# 09-PL_BANKS_34_35.net
KiCad netlist of a schematic drawn in Altium Designer
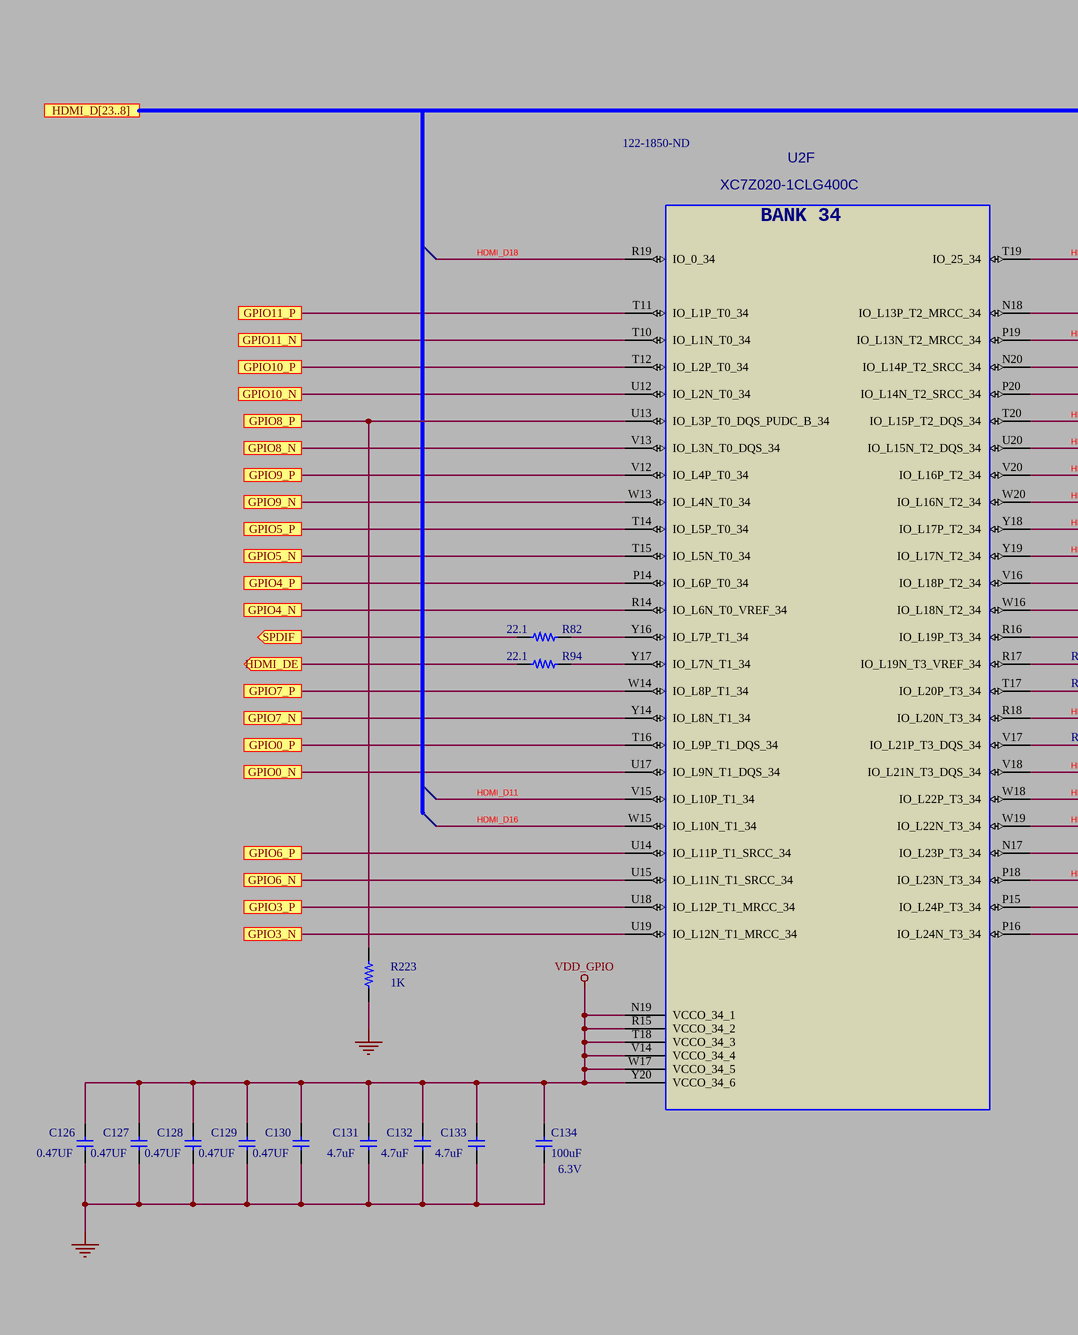
[diagram p0: 09-PL BANKS 34 & 35.SchDoc, left]
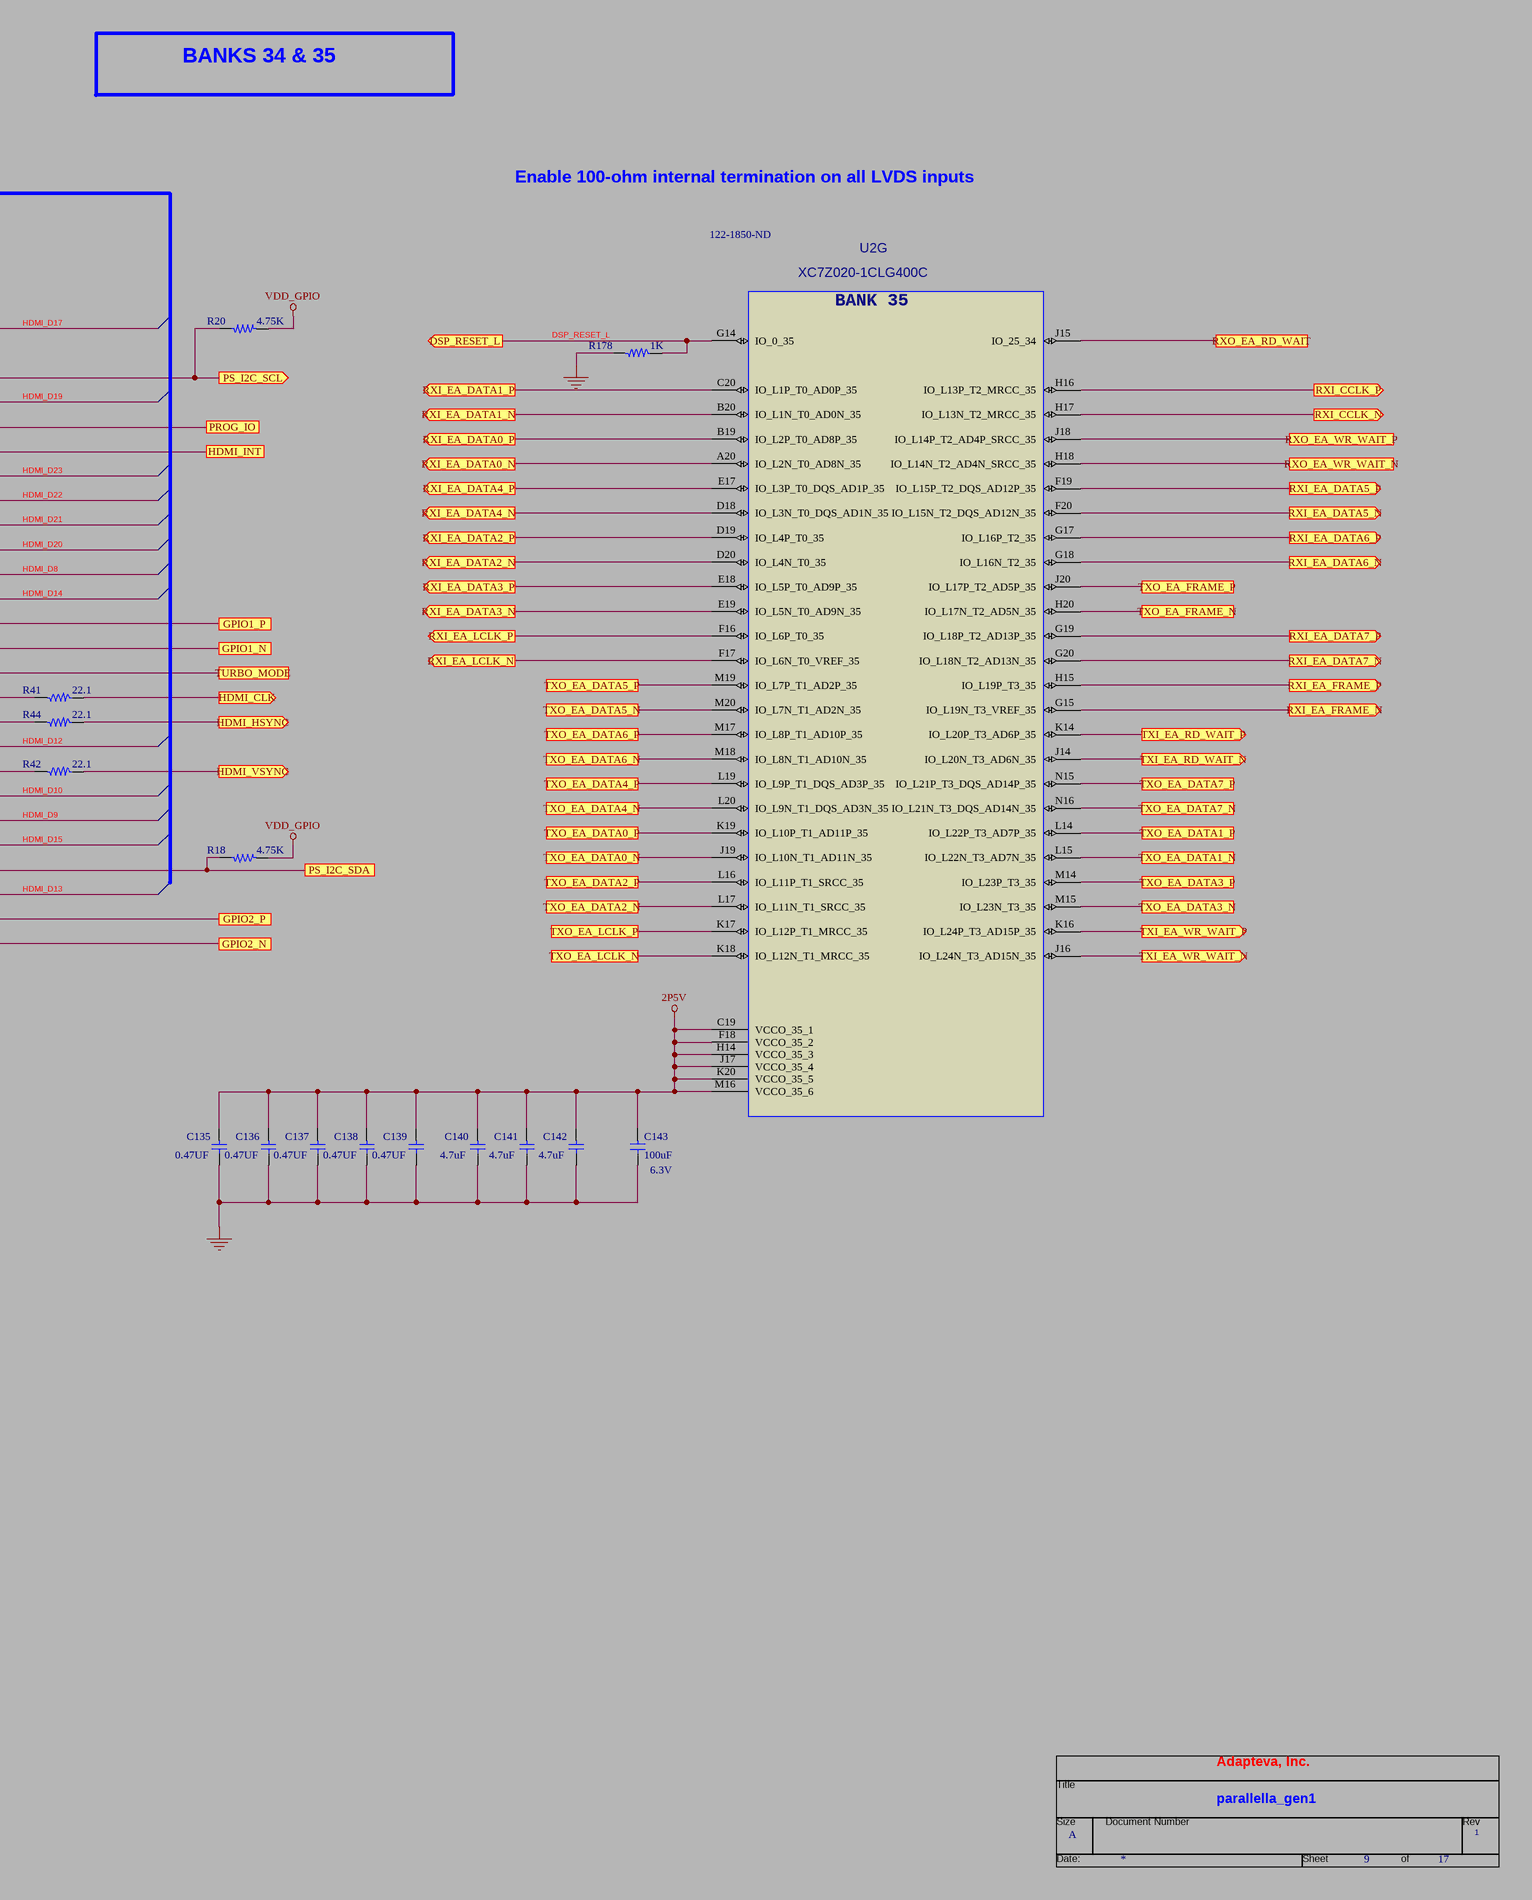
[diagram p1: 09-PL BANKS 34 & 35.SchDoc, right]

(export (version "E")
  (design (tool "Eeschema 10.0.6"))
  (components
    (comp (ref "C126")
      (value "0.47UF")
      (footprint "C0402")
      (description "CAP, 0402, 0.47UF, X5R, 16V")
      (fields (field (name "MFG") "TDK") (field (name "MFG PART NO") "C1005X5R1C474K"))
      (libsource (lib "*") (part "CAP0402_0P47UF_X5R"))
    )
    (comp (ref "C127")
      (value "0.47UF")
      (footprint "C0402")
      (description "CAP, 0402, 0.47UF, X5R, 16V")
      (fields (field (name "MFG") "TDK") (field (name "MFG PART NO") "C1005X5R1C474K"))
      (libsource (lib "*") (part "CAP0402_0P47UF_X5R"))
    )
    (comp (ref "C128")
      (value "0.47UF")
      (footprint "C0402")
      (description "CAP, 0402, 0.47UF, X5R, 16V")
      (fields (field (name "MFG") "TDK") (field (name "MFG PART NO") "C1005X5R1C474K"))
      (libsource (lib "*") (part "CAP0402_0P47UF_X5R"))
    )
    (comp (ref "C129")
      (value "0.47UF")
      (footprint "C0402")
      (description "CAP, 0402, 0.47UF, X5R, 16V")
      (fields (field (name "MFG") "TDK") (field (name "MFG PART NO") "C1005X5R1C474K"))
      (libsource (lib "*") (part "CAP0402_0P47UF_X5R"))
    )
    (comp (ref "C130")
      (value "0.47UF")
      (footprint "C0402")
      (description "CAP, 0402, 0.47UF, X5R, 16V")
      (fields (field (name "MFG") "TDK") (field (name "MFG PART NO") "C1005X5R1C474K"))
      (libsource (lib "*") (part "CAP0402_0P47UF_X5R"))
    )
    (comp (ref "C131")
      (value "4.7uF")
      (footprint "C0402")
      (description "CAP, 0402, 4.7UF, X5R, 6.3V")
      (fields (field (name "MFG PART NO") "C1005X5R0J475K") (field (name "MFG") "TDK"))
      (libsource (lib "*") (part "CAP0402_4P7UF_X5R"))
    )
    (comp (ref "C132")
      (value "4.7uF")
      (footprint "C0402")
      (description "CAP, 0402, 4.7UF, X5R, 6.3V")
      (fields (field (name "MFG PART NO") "C1005X5R0J475K") (field (name "MFG") "TDK"))
      (libsource (lib "*") (part "CAP0402_4P7UF_X5R"))
    )
    (comp (ref "C133")
      (value "4.7uF")
      (footprint "C0402")
      (description "CAP, 0402, 4.7UF, X5R, 6.3V")
      (fields (field (name "MFG PART NO") "C1005X5R0J475K") (field (name "MFG") "TDK"))
      (libsource (lib "*") (part "CAP0402_4P7UF_X5R"))
    )
    (comp (ref "C134")
      (value "100uF")
      (footprint "C1210")
      (description "CAP, 1210, 100UF, X5R, 6.3V, LOW ESR")
      (fields
        (field (name "VOLTAGE") "6.3V")
        (field (name "MFG PART NO") "GRM32ER60J107ME20L")
        (field (name "MFG") "MURATA")
      )
      (libsource (lib "*") (part "CAP1210_100UF_X5R_LOESR"))
    )
    (comp (ref "C135")
      (value "0.47UF")
      (footprint "C0402")
      (description "CAP, 0402, 0.47UF, X5R, 16V")
      (fields (field (name "MFG") "TDK") (field (name "MFG PART NO") "C1005X5R1C474K"))
      (libsource (lib "*") (part "CAP0402_0P47UF_X5R"))
    )
    (comp (ref "C136")
      (value "0.47UF")
      (footprint "C0402")
      (description "CAP, 0402, 0.47UF, X5R, 16V")
      (fields (field (name "MFG") "TDK") (field (name "MFG PART NO") "C1005X5R1C474K"))
      (libsource (lib "*") (part "CAP0402_0P47UF_X5R"))
    )
    (comp (ref "C137")
      (value "0.47UF")
      (footprint "C0402")
      (description "CAP, 0402, 0.47UF, X5R, 16V")
      (fields (field (name "MFG") "TDK") (field (name "MFG PART NO") "C1005X5R1C474K"))
      (libsource (lib "*") (part "CAP0402_0P47UF_X5R"))
    )
    (comp (ref "C138")
      (value "0.47UF")
      (footprint "C0402")
      (description "CAP, 0402, 0.47UF, X5R, 16V")
      (fields (field (name "MFG") "TDK") (field (name "MFG PART NO") "C1005X5R1C474K"))
      (libsource (lib "*") (part "CAP0402_0P47UF_X5R"))
    )
    (comp (ref "C139")
      (value "0.47UF")
      (footprint "C0402")
      (description "CAP, 0402, 0.47UF, X5R, 16V")
      (fields (field (name "MFG") "TDK") (field (name "MFG PART NO") "C1005X5R1C474K"))
      (libsource (lib "*") (part "CAP0402_0P47UF_X5R"))
    )
    (comp (ref "C140")
      (value "4.7uF")
      (footprint "C0402")
      (description "CAP, 0402, 4.7UF, X5R, 6.3V")
      (fields (field (name "MFG PART NO") "C1005X5R0J475K") (field (name "MFG") "TDK"))
      (libsource (lib "*") (part "CAP0402_4P7UF_X5R"))
    )
    (comp (ref "C141")
      (value "4.7uF")
      (footprint "C0402")
      (description "CAP, 0402, 4.7UF, X5R, 6.3V")
      (fields (field (name "MFG PART NO") "C1005X5R0J475K") (field (name "MFG") "TDK"))
      (libsource (lib "*") (part "CAP0402_4P7UF_X5R"))
    )
    (comp (ref "C142")
      (value "4.7uF")
      (footprint "C0402")
      (description "CAP, 0402, 4.7UF, X5R, 6.3V")
      (fields (field (name "MFG PART NO") "C1005X5R0J475K") (field (name "MFG") "TDK"))
      (libsource (lib "*") (part "CAP0402_4P7UF_X5R"))
    )
    (comp (ref "C143")
      (value "100uF")
      (footprint "C1210")
      (description "CAP, 1210, 100UF, X5R, 6.3V, LOW ESR")
      (fields
        (field (name "VOLTAGE") "6.3V")
        (field (name "MFG PART NO") "GRM32ER60J107ME20L")
        (field (name "MFG") "MURATA")
      )
      (libsource (lib "*") (part "CAP1210_100UF_X5R_LOESR"))
    )
    (comp (ref "R18")
      (value "4.75K")
      (footprint "R0402")
      (description "RES, 0402, 4.75K, 1%")
      (fields (field (name "MFG") "VISHAY") (field (name "MFG PART NO") "CRCW04024K75FKED"))
      (libsource (lib "*") (part "RES0402_4K75"))
    )
    (comp (ref "R20")
      (value "4.75K")
      (footprint "R0402")
      (description "RES, 0402, 4.75K, 1%")
      (fields (field (name "MFG") "VISHAY") (field (name "MFG PART NO") "CRCW04024K75FKED"))
      (libsource (lib "*") (part "RES0402_4K75"))
    )
    (comp (ref "R41")
      (value "22.1")
      (footprint "R0402")
      (description "RES, 0402, 22.1, 1%")
      (fields (field (name "MFG") "VISHAY") (field (name "MFG PART NO") "CRCW040222R1FKED"))
      (libsource (lib "*") (part "RES0402_22R1"))
    )
    (comp (ref "R42")
      (value "22.1")
      (footprint "R0402")
      (description "RES, 0402, 22.1, 1%")
      (fields (field (name "MFG") "VISHAY") (field (name "MFG PART NO") "CRCW040222R1FKED"))
      (libsource (lib "*") (part "RES0402_22R1"))
    )
    (comp (ref "R44")
      (value "22.1")
      (footprint "R0402")
      (description "RES, 0402, 22.1, 1%")
      (fields (field (name "MFG") "VISHAY") (field (name "MFG PART NO") "CRCW040222R1FKED"))
      (libsource (lib "*") (part "RES0402_22R1"))
    )
    (comp (ref "R82")
      (value "22.1")
      (footprint "R0402")
      (description "RES, 0402, 22.1, 1%")
      (fields (field (name "MFG") "VISHAY") (field (name "MFG PART NO") "CRCW040222R1FKED"))
      (libsource (lib "*") (part "RES0402_22R1"))
    )
    (comp (ref "R94")
      (value "22.1")
      (footprint "R0402")
      (description "RES, 0402, 22.1, 1%")
      (fields (field (name "MFG") "VISHAY") (field (name "MFG PART NO") "CRCW040222R1FKED"))
      (libsource (lib "*") (part "RES0402_22R1"))
    )
    (comp (ref "R178")
      (value "1K")
      (footprint "R0402")
      (description "RES, 0402, 1K")
      (fields (field (name "MFG") "VISHAY") (field (name "MFG PART NO") "CRCW04021K00FKED"))
      (libsource (lib "*") (part "RES0402_1K"))
    )
    (comp (ref "R223")
      (value "1K")
      (footprint "R0402")
      (description "RES, 0402, 1K")
      (fields (field (name "MFG") "VISHAY") (field (name "MFG PART NO") "CRCW04021K00FKED"))
      (libsource (lib "*") (part "RES0402_1K"))
    )
    (comp (ref "U2")
      (value "7Z020-CLG400")
      (footprint "CBGA400_17SQ_1P6H_P8MMP")
      (description "IC, EPP, XILINX, ZYNQ, 7Z020, CLG400")
      (fields
        (field (name "VENDOR PN") "XC7Z020-1CLG400C")
        (field (name "SUPPLIER PART NUMBER 1") "122-1850-ND")
      )
      (libsource (lib "*") (part "ZYNQ_7Z020_CLG400"))
    )
  )
  (nets
    (net (code "1") (name "/DSP_RESET_L") (class "Default")
      (node (ref "R178") (pin "2") (pinfunction "2_2") (pintype "passive"))
      (node (ref "U2") (pin "G14") (pinfunction "IO_0_35_G14") (pintype "bidirectional"))
    )
    (net (code "2") (name "/GPIO0_N") (class "Default")
      (node (ref "U2") (pin "U17") (pinfunction "IO_L9N_T1_DQS_34_U17") (pintype "bidirectional"))
    )
    (net (code "3") (name "/GPIO0_P") (class "Default")
      (node (ref "U2") (pin "T16") (pinfunction "IO_L9P_T1_DQS_34_T16") (pintype "bidirectional"))
    )
    (net (code "4") (name "/GPIO1_N") (class "Default")
      (node (ref "U2") (pin "W16") (pinfunction "IO_L18N_T2_34_W16") (pintype "bidirectional"))
    )
    (net (code "5") (name "/GPIO1_P") (class "Default")
      (node (ref "U2") (pin "V16") (pinfunction "IO_L18P_T2_34_V16") (pintype "bidirectional"))
    )
    (net (code "6") (name "/GPIO2_N") (class "Default")
      (node (ref "U2") (pin "P16") (pinfunction "IO_L24N_T3_34_P16") (pintype "bidirectional"))
    )
    (net (code "7") (name "/GPIO2_P") (class "Default")
      (node (ref "U2") (pin "P15") (pinfunction "IO_L24P_T3_34_P15") (pintype "bidirectional"))
    )
    (net (code "8") (name "/GPIO3_N") (class "Default")
      (node (ref "U2") (pin "U19") (pinfunction "IO_L12N_T1_MRCC_34_U19") (pintype "bidirectional"))
    )
    (net (code "9") (name "/GPIO3_P") (class "Default")
      (node (ref "U2") (pin "U18") (pinfunction "IO_L12P_T1_MRCC_34_U18") (pintype "bidirectional"))
    )
    (net (code "10") (name "/GPIO4_N") (class "Default")
      (node (ref "U2") (pin "R14") (pinfunction "IO_L6N_T0_VREF_34_R14") (pintype "bidirectional"))
    )
    (net (code "11") (name "/GPIO4_P") (class "Default")
      (node (ref "U2") (pin "P14") (pinfunction "IO_L6P_T0_34_P14") (pintype "bidirectional"))
    )
    (net (code "12") (name "/GPIO5_N") (class "Default")
      (node (ref "U2") (pin "T15") (pinfunction "IO_L5N_T0_34_T15") (pintype "bidirectional"))
    )
    (net (code "13") (name "/GPIO5_P") (class "Default")
      (node (ref "U2") (pin "T14") (pinfunction "IO_L5P_T0_34_T14") (pintype "bidirectional"))
    )
    (net (code "14") (name "/GPIO6_N") (class "Default")
      (node (ref "U2") (pin "U15") (pinfunction "IO_L11N_T1_SRCC_34_U15") (pintype "bidirectional"))
    )
    (net (code "15") (name "/GPIO6_P") (class "Default")
      (node (ref "U2") (pin "U14") (pinfunction "IO_L11P_T1_SRCC_34_U14") (pintype "bidirectional"))
    )
    (net (code "16") (name "/GPIO7_N") (class "Default")
      (node (ref "U2") (pin "Y14") (pinfunction "IO_L8N_T1_34_Y14") (pintype "bidirectional"))
    )
    (net (code "17") (name "/GPIO7_P") (class "Default")
      (node (ref "U2") (pin "W14") (pinfunction "IO_L8P_T1_34_W14") (pintype "bidirectional"))
    )
    (net (code "18") (name "/GPIO8_N") (class "Default")
      (node (ref "U2") (pin "V13") (pinfunction "IO_L3N_T0_DQS_34_V13") (pintype "bidirectional"))
    )
    (net (code "19") (name "/GPIO8_P") (class "Default")
      (node (ref "R223") (pin "2") (pinfunction "2_2") (pintype "passive"))
      (node (ref "U2") (pin "U13") (pinfunction "IO_L3P_T0_DQS_PUDC_B_34_U13") (pintype "bidirectional"))
    )
    (net (code "20") (name "/GPIO9_N") (class "Default")
      (node (ref "U2") (pin "W13") (pinfunction "IO_L4N_T0_34_W13") (pintype "bidirectional"))
    )
    (net (code "21") (name "/GPIO9_P") (class "Default")
      (node (ref "U2") (pin "V12") (pinfunction "IO_L4P_T0_34_V12") (pintype "bidirectional"))
    )
    (net (code "22") (name "/GPIO10_N") (class "Default")
      (node (ref "U2") (pin "U12") (pinfunction "IO_L2N_T0_34_U12") (pintype "bidirectional"))
    )
    (net (code "23") (name "/GPIO10_P") (class "Default")
      (node (ref "U2") (pin "T12") (pinfunction "IO_L2P_T0_34_T12") (pintype "bidirectional"))
    )
    (net (code "24") (name "/GPIO11_N") (class "Default")
      (node (ref "U2") (pin "T10") (pinfunction "IO_L1N_T0_34_T10") (pintype "bidirectional"))
    )
    (net (code "25") (name "/GPIO11_P") (class "Default")
      (node (ref "U2") (pin "T11") (pinfunction "IO_L1P_T0_34_T11") (pintype "bidirectional"))
    )
    (net (code "26") (name "/HDMI_CLK") (class "Default")
      (node (ref "R41") (pin "2") (pinfunction "2_2") (pintype "passive"))
    )
    (net (code "27") (name "/HDMI_D8") (class "Default")
      (node (ref "U2") (pin "Y18") (pinfunction "IO_L17P_T2_34_Y18") (pintype "bidirectional"))
    )
    (net (code "28") (name "/HDMI_D9") (class "Default")
      (node (ref "U2") (pin "W18") (pinfunction "IO_L22P_T3_34_W18") (pintype "bidirectional"))
    )
    (net (code "29") (name "/HDMI_D10") (class "Default")
      (node (ref "U2") (pin "V18") (pinfunction "IO_L21N_T3_DQS_34_V18") (pintype "bidirectional"))
    )
    (net (code "30") (name "/HDMI_D11") (class "Default")
      (node (ref "U2") (pin "V15") (pinfunction "IO_L10P_T1_34_V15") (pintype "bidirectional"))
    )
    (net (code "31") (name "/HDMI_D12") (class "Default")
      (node (ref "U2") (pin "R18") (pinfunction "IO_L20N_T3_34_R18") (pintype "bidirectional"))
    )
    (net (code "32") (name "/HDMI_D13") (class "Default")
      (node (ref "U2") (pin "P18") (pinfunction "IO_L23N_T3_34_P18") (pintype "bidirectional"))
    )
    (net (code "33") (name "/HDMI_D14") (class "Default")
      (node (ref "U2") (pin "Y19") (pinfunction "IO_L17N_T2_34_Y19") (pintype "bidirectional"))
    )
    (net (code "34") (name "/HDMI_D15") (class "Default")
      (node (ref "U2") (pin "W19") (pinfunction "IO_L22N_T3_34_W19") (pintype "bidirectional"))
    )
    (net (code "35") (name "/HDMI_D16") (class "Default")
      (node (ref "U2") (pin "W15") (pinfunction "IO_L10N_T1_34_W15") (pintype "bidirectional"))
    )
    (net (code "36") (name "/HDMI_D17") (class "Default")
      (node (ref "U2") (pin "T19") (pinfunction "IO_25_34_T19") (pintype "bidirectional"))
    )
    (net (code "37") (name "/HDMI_D18") (class "Default")
      (node (ref "U2") (pin "R19") (pinfunction "IO_0_34_R19") (pintype "bidirectional"))
    )
    (net (code "38") (name "/HDMI_D19") (class "Default")
      (node (ref "U2") (pin "P19") (pinfunction "IO_L13N_T2_MRCC_34_P19") (pintype "bidirectional"))
    )
    (net (code "39") (name "/HDMI_D20") (class "Default")
      (node (ref "U2") (pin "W20") (pinfunction "IO_L16N_T2_34_W20") (pintype "bidirectional"))
    )
    (net (code "40") (name "/HDMI_D21") (class "Default")
      (node (ref "U2") (pin "V20") (pinfunction "IO_L16P_T2_34_V20") (pintype "bidirectional"))
    )
    (net (code "41") (name "/HDMI_D22") (class "Default")
      (node (ref "U2") (pin "U20") (pinfunction "IO_L15N_T2_DQS_34_U20") (pintype "bidirectional"))
    )
    (net (code "42") (name "/HDMI_D23") (class "Default")
      (node (ref "U2") (pin "T20") (pinfunction "IO_L15P_T2_DQS_34_T20") (pintype "bidirectional"))
    )
    (net (code "43") (name "/HDMI_DE") (class "Default")
      (node (ref "R94") (pin "2") (pinfunction "2_2") (pintype "passive"))
    )
    (net (code "45") (name "/HDMI_HSYNC") (class "Default")
      (node (ref "R44") (pin "2") (pinfunction "2_2") (pintype "passive"))
    )
    (net (code "46") (name "/HDMI_INT") (class "Default")
      (node (ref "U2") (pin "P20") (pinfunction "IO_L14N_T2_SRCC_34_P20") (pintype "bidirectional"))
    )
    (net (code "47") (name "/HDMI_VSYNC") (class "Default")
      (node (ref "R42") (pin "2") (pinfunction "2_2") (pintype "passive"))
    )
    (net (code "48") (name "/PROG_IO") (class "Default")
      (node (ref "U2") (pin "N20") (pinfunction "IO_L14P_T2_SRCC_34_N20") (pintype "bidirectional"))
    )
    (net (code "49") (name "/PS_I2C_SCL") (class "Default")
      (node (ref "R20") (pin "2") (pinfunction "2_2") (pintype "passive"))
      (node (ref "U2") (pin "N18") (pinfunction "IO_L13P_T2_MRCC_34_N18") (pintype "bidirectional"))
    )
    (net (code "50") (name "/PS_I2C_SDA") (class "Default")
      (node (ref "R18") (pin "2") (pinfunction "2_2") (pintype "passive"))
      (node (ref "U2") (pin "N17") (pinfunction "IO_L23P_T3_34_N17") (pintype "bidirectional"))
    )
    (net (code "51") (name "/RXI_CCLK_N") (class "Default")
      (node (ref "U2") (pin "H17") (pinfunction "IO_L13N_T2_MRCC_35_H17") (pintype "bidirectional"))
    )
    (net (code "52") (name "/RXI_CCLK_P") (class "Default")
      (node (ref "U2") (pin "H16") (pinfunction "IO_L13P_T2_MRCC_35_H16") (pintype "bidirectional"))
    )
    (net (code "53") (name "/RXI_EA_DATA0_N") (class "Default")
      (node (ref "U2") (pin "A20") (pinfunction "IO_L2N_T0_AD8N_35_A20") (pintype "bidirectional"))
    )
    (net (code "54") (name "/RXI_EA_DATA0_P") (class "Default")
      (node (ref "U2") (pin "B19") (pinfunction "IO_L2P_T0_AD8P_35_B19") (pintype "bidirectional"))
    )
    (net (code "55") (name "/RXI_EA_DATA1_N") (class "Default")
      (node (ref "U2") (pin "B20") (pinfunction "IO_L1N_T0_AD0N_35_B20") (pintype "bidirectional"))
    )
    (net (code "56") (name "/RXI_EA_DATA1_P") (class "Default")
      (node (ref "U2") (pin "C20") (pinfunction "IO_L1P_T0_AD0P_35_C20") (pintype "bidirectional"))
    )
    (net (code "57") (name "/RXI_EA_DATA2_N") (class "Default")
      (node (ref "U2") (pin "D20") (pinfunction "IO_L4N_T0_35_D20") (pintype "bidirectional"))
    )
    (net (code "58") (name "/RXI_EA_DATA2_P") (class "Default")
      (node (ref "U2") (pin "D19") (pinfunction "IO_L4P_T0_35_D19") (pintype "bidirectional"))
    )
    (net (code "59") (name "/RXI_EA_DATA3_N") (class "Default")
      (node (ref "U2") (pin "E19") (pinfunction "IO_L5N_T0_AD9N_35_E19") (pintype "bidirectional"))
    )
    (net (code "60") (name "/RXI_EA_DATA3_P") (class "Default")
      (node (ref "U2") (pin "E18") (pinfunction "IO_L5P_T0_AD9P_35_E18") (pintype "bidirectional"))
    )
    (net (code "61") (name "/RXI_EA_DATA4_N") (class "Default")
      (node (ref "U2") (pin "D18") (pinfunction "IO_L3N_T0_DQS_AD1N_35_D18") (pintype "bidirectional"))
    )
    (net (code "62") (name "/RXI_EA_DATA4_P") (class "Default")
      (node (ref "U2") (pin "E17") (pinfunction "IO_L3P_T0_DQS_AD1P_35_E17") (pintype "bidirectional"))
    )
    (net (code "63") (name "/RXI_EA_DATA5_N") (class "Default")
      (node (ref "U2") (pin "F20") (pinfunction "IO_L15N_T2_DQS_AD12N_35_F20") (pintype "bidirectional"))
    )
    (net (code "64") (name "/RXI_EA_DATA5_P") (class "Default")
      (node (ref "U2") (pin "F19") (pinfunction "IO_L15P_T2_DQS_AD12P_35_F19") (pintype "bidirectional"))
    )
    (net (code "65") (name "/RXI_EA_DATA6_N") (class "Default")
      (node (ref "U2") (pin "G18") (pinfunction "IO_L16N_T2_35_G18") (pintype "bidirectional"))
    )
    (net (code "66") (name "/RXI_EA_DATA6_P") (class "Default")
      (node (ref "U2") (pin "G17") (pinfunction "IO_L16P_T2_35_G17") (pintype "bidirectional"))
    )
    (net (code "67") (name "/RXI_EA_DATA7_N") (class "Default")
      (node (ref "U2") (pin "G20") (pinfunction "IO_L18N_T2_AD13N_35_G20") (pintype "bidirectional"))
    )
    (net (code "68") (name "/RXI_EA_DATA7_P") (class "Default")
      (node (ref "U2") (pin "G19") (pinfunction "IO_L18P_T2_AD13P_35_G19") (pintype "bidirectional"))
    )
    (net (code "69") (name "/RXI_EA_FRAME_N") (class "Default")
      (node (ref "U2") (pin "G15") (pinfunction "IO_L19N_T3_VREF_35_G15") (pintype "bidirectional"))
    )
    (net (code "70") (name "/RXI_EA_FRAME_P") (class "Default")
      (node (ref "U2") (pin "H15") (pinfunction "IO_L19P_T3_35_H15") (pintype "bidirectional"))
    )
    (net (code "71") (name "/RXI_EA_LCLK_N") (class "Default")
      (node (ref "U2") (pin "F17") (pinfunction "IO_L6N_T0_VREF_35_F17") (pintype "bidirectional"))
    )
    (net (code "72") (name "/RXI_EA_LCLK_P") (class "Default")
      (node (ref "U2") (pin "F16") (pinfunction "IO_L6P_T0_35_F16") (pintype "bidirectional"))
    )
    (net (code "73") (name "/RXO_EA_RD_WAIT") (class "Default")
      (node (ref "U2") (pin "J15") (pinfunction "IO_25_34_J15") (pintype "bidirectional"))
    )
    (net (code "74") (name "/RXO_EA_WR_WAIT_N") (class "Default")
      (node (ref "U2") (pin "H18") (pinfunction "IO_L14N_T2_AD4N_SRCC_35_H18") (pintype "bidirectional"))
    )
    (net (code "75") (name "/RXO_EA_WR_WAIT_P") (class "Default")
      (node (ref "U2") (pin "J18") (pinfunction "IO_L14P_T2_AD4P_SRCC_35_J18") (pintype "bidirectional"))
    )
    (net (code "76") (name "/SPDIF") (class "Default")
      (node (ref "R82") (pin "2") (pinfunction "2_2") (pintype "passive"))
    )
    (net (code "77") (name "/TURBO_MODE") (class "Default")
      (node (ref "U2") (pin "R16") (pinfunction "IO_L19P_T3_34_R16") (pintype "bidirectional"))
    )
    (net (code "78") (name "/TXI_EA_RD_WAIT_N") (class "Default")
      (node (ref "U2") (pin "J14") (pinfunction "IO_L20N_T3_AD6N_35_J14") (pintype "bidirectional"))
    )
    (net (code "79") (name "/TXI_EA_RD_WAIT_P") (class "Default")
      (node (ref "U2") (pin "K14") (pinfunction "IO_L20P_T3_AD6P_35_K14") (pintype "bidirectional"))
    )
    (net (code "80") (name "/TXI_EA_WR_WAIT_N") (class "Default")
      (node (ref "U2") (pin "J16") (pinfunction "IO_L24N_T3_AD15N_35_J16") (pintype "bidirectional"))
    )
    (net (code "81") (name "/TXI_EA_WR_WAIT_P") (class "Default")
      (node (ref "U2") (pin "K16") (pinfunction "IO_L24P_T3_AD15P_35_K16") (pintype "bidirectional"))
    )
    (net (code "82") (name "/TXO_EA_DATA0_N") (class "Default")
      (node (ref "U2") (pin "J19") (pinfunction "IO_L10N_T1_AD11N_35_J19") (pintype "bidirectional"))
    )
    (net (code "83") (name "/TXO_EA_DATA0_P") (class "Default")
      (node (ref "U2") (pin "K19") (pinfunction "IO_L10P_T1_AD11P_35_K19") (pintype "bidirectional"))
    )
    (net (code "84") (name "/TXO_EA_DATA1_N") (class "Default")
      (node (ref "U2") (pin "L15") (pinfunction "IO_L22N_T3_AD7N_35_L15") (pintype "bidirectional"))
    )
    (net (code "85") (name "/TXO_EA_DATA1_P") (class "Default")
      (node (ref "U2") (pin "L14") (pinfunction "IO_L22P_T3_AD7P_35_L14") (pintype "bidirectional"))
    )
    (net (code "86") (name "/TXO_EA_DATA2_N") (class "Default")
      (node (ref "U2") (pin "L17") (pinfunction "IO_L11N_T1_SRCC_35_L17") (pintype "bidirectional"))
    )
    (net (code "87") (name "/TXO_EA_DATA2_P") (class "Default")
      (node (ref "U2") (pin "L16") (pinfunction "IO_L11P_T1_SRCC_35_L16") (pintype "bidirectional"))
    )
    (net (code "88") (name "/TXO_EA_DATA3_N") (class "Default")
      (node (ref "U2") (pin "M15") (pinfunction "IO_L23N_T3_35_M15") (pintype "bidirectional"))
    )
    (net (code "89") (name "/TXO_EA_DATA3_P") (class "Default")
      (node (ref "U2") (pin "M14") (pinfunction "IO_L23P_T3_35_M14") (pintype "bidirectional"))
    )
    (net (code "90") (name "/TXO_EA_DATA4_N") (class "Default")
      (node (ref "U2") (pin "L20") (pinfunction "IO_L9N_T1_DQS_AD3N_35_L20") (pintype "bidirectional"))
    )
    (net (code "91") (name "/TXO_EA_DATA4_P") (class "Default")
      (node (ref "U2") (pin "L19") (pinfunction "IO_L9P_T1_DQS_AD3P_35_L19") (pintype "bidirectional"))
    )
    (net (code "92") (name "/TXO_EA_DATA5_N") (class "Default")
      (node (ref "U2") (pin "M20") (pinfunction "IO_L7N_T1_AD2N_35_M20") (pintype "bidirectional"))
    )
    (net (code "93") (name "/TXO_EA_DATA5_P") (class "Default")
      (node (ref "U2") (pin "M19") (pinfunction "IO_L7P_T1_AD2P_35_M19") (pintype "bidirectional"))
    )
    (net (code "94") (name "/TXO_EA_DATA6_N") (class "Default")
      (node (ref "U2") (pin "M18") (pinfunction "IO_L8N_T1_AD10N_35_M18") (pintype "bidirectional"))
    )
    (net (code "95") (name "/TXO_EA_DATA6_P") (class "Default")
      (node (ref "U2") (pin "M17") (pinfunction "IO_L8P_T1_AD10P_35_M17") (pintype "bidirectional"))
    )
    (net (code "96") (name "/TXO_EA_DATA7_N") (class "Default")
      (node (ref "U2") (pin "N16") (pinfunction "IO_L21N_T3_DQS_AD14N_35_N16") (pintype "bidirectional"))
    )
    (net (code "97") (name "/TXO_EA_DATA7_P") (class "Default")
      (node (ref "U2") (pin "N15") (pinfunction "IO_L21P_T3_DQS_AD14P_35_N15") (pintype "bidirectional"))
    )
    (net (code "98") (name "/TXO_EA_FRAME_N") (class "Default")
      (node (ref "U2") (pin "H20") (pinfunction "IO_L17N_T2_AD5N_35_H20") (pintype "bidirectional"))
    )
    (net (code "99") (name "/TXO_EA_FRAME_P") (class "Default")
      (node (ref "U2") (pin "J20") (pinfunction "IO_L17P_T2_AD5P_35_J20") (pintype "bidirectional"))
    )
    (net (code "100") (name "/TXO_EA_LCLK_N") (class "Default")
      (node (ref "U2") (pin "K18") (pinfunction "IO_L12N_T1_MRCC_35_K18") (pintype "bidirectional"))
    )
    (net (code "101") (name "/TXO_EA_LCLK_P") (class "Default")
      (node (ref "U2") (pin "K17") (pinfunction "IO_L12P_T1_MRCC_35_K17") (pintype "bidirectional"))
    )
    (net (code "102") (name "2P5V") (class "Default")
      (node (ref "C135") (pin "1") (pinfunction "1_1") (pintype "passive"))
      (node (ref "C136") (pin "1") (pinfunction "1_1") (pintype "passive"))
      (node (ref "C137") (pin "1") (pinfunction "1_1") (pintype "passive"))
      (node (ref "C138") (pin "1") (pinfunction "1_1") (pintype "passive"))
      (node (ref "C139") (pin "1") (pinfunction "1_1") (pintype "passive"))
      (node (ref "C140") (pin "1") (pinfunction "1_1") (pintype "passive"))
      (node (ref "C141") (pin "1") (pinfunction "1_1") (pintype "passive"))
      (node (ref "C142") (pin "1") (pinfunction "1_1") (pintype "passive"))
      (node (ref "C143") (pin "1") (pinfunction "1_1") (pintype "passive"))
      (node (ref "U2") (pin "C19") (pinfunction "VCCO_35_1_C19") (pintype "power_in"))
      (node (ref "U2") (pin "F18") (pinfunction "VCCO_35_2_F18") (pintype "power_in"))
      (node (ref "U2") (pin "H14") (pinfunction "VCCO_35_3_H14") (pintype "power_in"))
      (node (ref "U2") (pin "J17") (pinfunction "VCCO_35_4_J17") (pintype "power_in"))
      (node (ref "U2") (pin "K20") (pinfunction "VCCO_35_5_K20") (pintype "power_in"))
      (node (ref "U2") (pin "M16") (pinfunction "VCCO_35_6_M16") (pintype "power_in"))
    )
    (net (code "103") (name "GND") (class "Default")
      (node (ref "C126") (pin "2") (pinfunction "2_2") (pintype "passive"))
      (node (ref "C127") (pin "2") (pinfunction "2_2") (pintype "passive"))
      (node (ref "C128") (pin "2") (pinfunction "2_2") (pintype "passive"))
      (node (ref "C129") (pin "2") (pinfunction "2_2") (pintype "passive"))
      (node (ref "C130") (pin "2") (pinfunction "2_2") (pintype "passive"))
      (node (ref "C131") (pin "2") (pinfunction "2_2") (pintype "passive"))
      (node (ref "C132") (pin "2") (pinfunction "2_2") (pintype "passive"))
      (node (ref "C133") (pin "2") (pinfunction "2_2") (pintype "passive"))
      (node (ref "C134") (pin "2") (pinfunction "2_2") (pintype "passive"))
      (node (ref "C135") (pin "2") (pinfunction "2_2") (pintype "passive"))
      (node (ref "C136") (pin "2") (pinfunction "2_2") (pintype "passive"))
      (node (ref "C137") (pin "2") (pinfunction "2_2") (pintype "passive"))
      (node (ref "C138") (pin "2") (pinfunction "2_2") (pintype "passive"))
      (node (ref "C139") (pin "2") (pinfunction "2_2") (pintype "passive"))
      (node (ref "C140") (pin "2") (pinfunction "2_2") (pintype "passive"))
      (node (ref "C141") (pin "2") (pinfunction "2_2") (pintype "passive"))
      (node (ref "C142") (pin "2") (pinfunction "2_2") (pintype "passive"))
      (node (ref "C143") (pin "2") (pinfunction "2_2") (pintype "passive"))
      (node (ref "R178") (pin "1") (pinfunction "1_1") (pintype "passive"))
      (node (ref "R223") (pin "1") (pinfunction "1_1") (pintype "passive"))
    )
    (net (code "104") (name "Net-(U2F-IO_L7N_T1_34)") (class "Default")
      (node (ref "R94") (pin "1") (pinfunction "1_1") (pintype "passive"))
      (node (ref "U2") (pin "Y17") (pinfunction "IO_L7N_T1_34_Y17") (pintype "bidirectional"))
    )
    (net (code "105") (name "Net-(U2F-IO_L7P_T1_34)") (class "Default")
      (node (ref "R82") (pin "1") (pinfunction "1_1") (pintype "passive"))
      (node (ref "U2") (pin "Y16") (pinfunction "IO_L7P_T1_34_Y16") (pintype "bidirectional"))
    )
    (net (code "106") (name "Net-(U2F-IO_L19N_T3_VREF_34)") (class "Default")
      (node (ref "R41") (pin "1") (pinfunction "1_1") (pintype "passive"))
      (node (ref "U2") (pin "R17") (pinfunction "IO_L19N_T3_VREF_34_R17") (pintype "bidirectional"))
    )
    (net (code "107") (name "Net-(U2F-IO_L20P_T3_34)") (class "Default")
      (node (ref "R44") (pin "1") (pinfunction "1_1") (pintype "passive"))
      (node (ref "U2") (pin "T17") (pinfunction "IO_L20P_T3_34_T17") (pintype "bidirectional"))
    )
    (net (code "108") (name "Net-(U2F-IO_L21P_T3_DQS_34)") (class "Default")
      (node (ref "R42") (pin "1") (pinfunction "1_1") (pintype "passive"))
      (node (ref "U2") (pin "V17") (pinfunction "IO_L21P_T3_DQS_34_V17") (pintype "bidirectional"))
    )
    (net (code "109") (name "VDD_GPIO") (class "Default")
      (node (ref "C126") (pin "1") (pinfunction "1_1") (pintype "passive"))
      (node (ref "C127") (pin "1") (pinfunction "1_1") (pintype "passive"))
      (node (ref "C128") (pin "1") (pinfunction "1_1") (pintype "passive"))
      (node (ref "C129") (pin "1") (pinfunction "1_1") (pintype "passive"))
      (node (ref "C130") (pin "1") (pinfunction "1_1") (pintype "passive"))
      (node (ref "C131") (pin "1") (pinfunction "1_1") (pintype "passive"))
      (node (ref "C132") (pin "1") (pinfunction "1_1") (pintype "passive"))
      (node (ref "C133") (pin "1") (pinfunction "1_1") (pintype "passive"))
      (node (ref "C134") (pin "1") (pinfunction "1_1") (pintype "passive"))
      (node (ref "R18") (pin "1") (pinfunction "1_1") (pintype "passive"))
      (node (ref "R20") (pin "1") (pinfunction "1_1") (pintype "passive"))
      (node (ref "U2") (pin "N19") (pinfunction "VCCO_34_1_N19") (pintype "power_in"))
      (node (ref "U2") (pin "R15") (pinfunction "VCCO_34_2_R15") (pintype "power_in"))
      (node (ref "U2") (pin "T18") (pinfunction "VCCO_34_3_T18") (pintype "power_in"))
      (node (ref "U2") (pin "V14") (pinfunction "VCCO_34_4_V14") (pintype "power_in"))
      (node (ref "U2") (pin "W17") (pinfunction "VCCO_34_5_W17") (pintype "power_in"))
      (node (ref "U2") (pin "Y20") (pinfunction "VCCO_34_6_Y20") (pintype "power_in"))
    )
  )
)
